# hhv-dcdarknet-varient-2.net
KiCad netlist of a schematic drawn in EAGLE
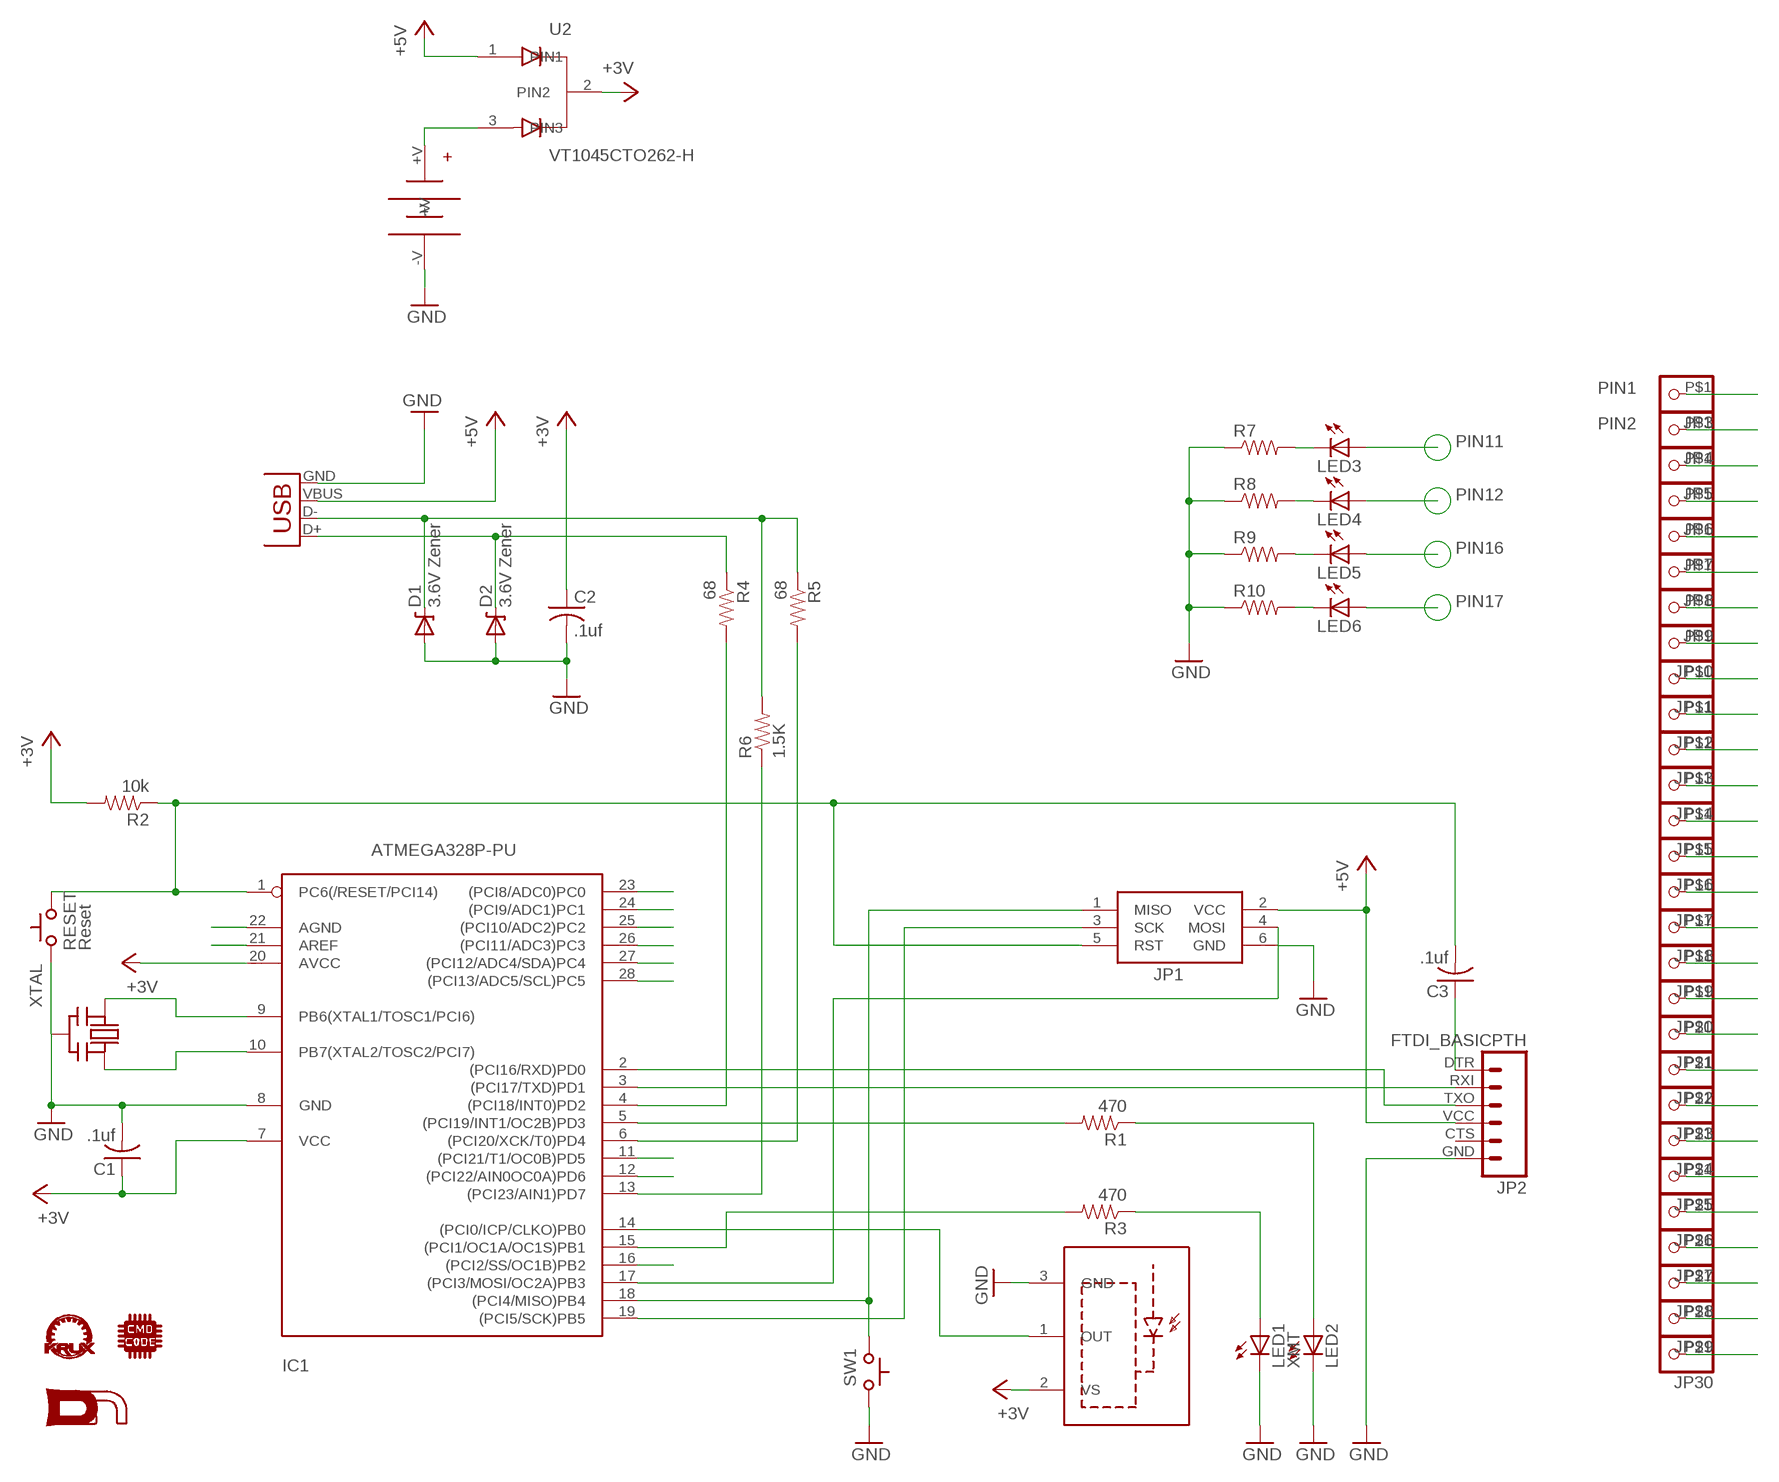
[diagram p0: schematic, sheet 1]

(export (version "E")
  (design (tool "Eeschema 10.0.6"))
  (components
    (comp (ref "C1")
      (value ".1uf")
      (footprint "eagle-import:C025-030X050")
      (libsource (lib "eagle-import") (part "C-US025-030X050"))
    )
    (comp (ref "C2")
      (value ".1uf")
      (footprint "eagle-import:C025-030X050")
      (libsource (lib "eagle-import") (part "C-US025-030X050"))
    )
    (comp (ref "C3")
      (value ".1uf")
      (footprint "eagle-import:C025-030X050")
      (libsource (lib "eagle-import") (part "C-US025-030X050"))
    )
    (comp (ref "D1")
      (value "3.6V Zener")
      (footprint "eagle-import:DIODE-ZENER")
      (libsource (lib "eagle-import") (part "DIODE-ZENERPTH"))
    )
    (comp (ref "D2")
      (value "3.6V Zener")
      (footprint "eagle-import:DIODE-ZENER")
      (libsource (lib "eagle-import") (part "DIODE-ZENERPTH"))
    )
    (comp (ref "IC1")
      (value "ATMEGA328P-PU")
      (footprint "eagle-import:DIL28-3")
      (libsource (lib "eagle-import") (part "ATMEGA168PV-10"))
    )
    (comp (ref "JP1")
      (value "JP1")
      (footprint "eagle-import:AVRISP")
      (libsource (lib "eagle-import") (part "AVRISP-6"))
    )
    (comp (ref "JP2")
      (value "FTDI_BASICPTH")
      (footprint "eagle-import:FTDI_BASIC")
      (libsource (lib "eagle-import") (part "FTDI_BASICPTH"))
    )
    (comp (ref "JP3")
      (value "PINHD-1X11X1_SQUARE")
      (footprint "eagle-import:1X1-SMALL_CUT")
      (libsource (lib "eagle-import") (part "PINHD-1X11X1_SQUARE"))
    )
    (comp (ref "JP4")
      (value "PINHD-1X11X1_SQUARE")
      (footprint "eagle-import:1X1-SMALL_CUT")
      (libsource (lib "eagle-import") (part "PINHD-1X11X1_SQUARE"))
    )
    (comp (ref "JP5")
      (value "PINHD-1X11X1_SQUARE")
      (footprint "eagle-import:1X1-SMALL_CUT")
      (libsource (lib "eagle-import") (part "PINHD-1X11X1_SQUARE"))
    )
    (comp (ref "JP6")
      (value "PINHD-1X11X1_SQUARE")
      (footprint "eagle-import:1X1-SMALL_CUT")
      (libsource (lib "eagle-import") (part "PINHD-1X11X1_SQUARE"))
    )
    (comp (ref "JP7")
      (value "PINHD-1X11X1_SQUARE")
      (footprint "eagle-import:1X1-SMALL_CUT")
      (libsource (lib "eagle-import") (part "PINHD-1X11X1_SQUARE"))
    )
    (comp (ref "JP8")
      (value "PINHD-1X11X1_SQUARE")
      (footprint "eagle-import:1X1-SMALL_CUT")
      (libsource (lib "eagle-import") (part "PINHD-1X11X1_SQUARE"))
    )
    (comp (ref "JP9")
      (value "PINHD-1X11X1_SQUARE")
      (footprint "eagle-import:1X1-SMALL_CUT")
      (libsource (lib "eagle-import") (part "PINHD-1X11X1_SQUARE"))
    )
    (comp (ref "JP10")
      (value "PINHD-1X11X1_SQUARE")
      (footprint "eagle-import:1X1-SMALL_CUT")
      (libsource (lib "eagle-import") (part "PINHD-1X11X1_SQUARE"))
    )
    (comp (ref "JP11")
      (value "PINHD-1X11X1_SQUARE")
      (footprint "eagle-import:1X1-SMALL_CUT")
      (libsource (lib "eagle-import") (part "PINHD-1X11X1_SQUARE"))
    )
    (comp (ref "JP12")
      (value "PINHD-1X11X1_SQUARE")
      (footprint "eagle-import:1X1-SMALL_CUT")
      (libsource (lib "eagle-import") (part "PINHD-1X11X1_SQUARE"))
    )
    (comp (ref "JP13")
      (value "PINHD-1X11X1_SQUARE")
      (footprint "eagle-import:1X1-SMALL_CUT")
      (libsource (lib "eagle-import") (part "PINHD-1X11X1_SQUARE"))
    )
    (comp (ref "JP14")
      (value "PINHD-1X11X1_SQUARE")
      (footprint "eagle-import:1X1-SMALL_CUT")
      (libsource (lib "eagle-import") (part "PINHD-1X11X1_SQUARE"))
    )
    (comp (ref "JP15")
      (value "PINHD-1X11X1_SQUARE")
      (footprint "eagle-import:1X1-SMALL_CUT")
      (libsource (lib "eagle-import") (part "PINHD-1X11X1_SQUARE"))
    )
    (comp (ref "JP16")
      (value "PINHD-1X11X1_SQUARE")
      (footprint "eagle-import:1X1-SMALL_CUT")
      (libsource (lib "eagle-import") (part "PINHD-1X11X1_SQUARE"))
    )
    (comp (ref "JP17")
      (value "PINHD-1X11X1_SQUARE")
      (footprint "eagle-import:1X1-SMALL_CUT")
      (libsource (lib "eagle-import") (part "PINHD-1X11X1_SQUARE"))
    )
    (comp (ref "JP18")
      (value "PINHD-1X11X1_SQUARE")
      (footprint "eagle-import:1X1-SMALL_CUT")
      (libsource (lib "eagle-import") (part "PINHD-1X11X1_SQUARE"))
    )
    (comp (ref "JP19")
      (value "PINHD-1X11X1_SQUARE")
      (footprint "eagle-import:1X1-SMALL_CUT")
      (libsource (lib "eagle-import") (part "PINHD-1X11X1_SQUARE"))
    )
    (comp (ref "JP20")
      (value "PINHD-1X11X1_SQUARE")
      (footprint "eagle-import:1X1-SMALL_CUT")
      (libsource (lib "eagle-import") (part "PINHD-1X11X1_SQUARE"))
    )
    (comp (ref "JP21")
      (value "PINHD-1X11X1_SQUARE")
      (footprint "eagle-import:1X1-SMALL_CUT")
      (libsource (lib "eagle-import") (part "PINHD-1X11X1_SQUARE"))
    )
    (comp (ref "JP22")
      (value "PINHD-1X11X1_SQUARE")
      (footprint "eagle-import:1X1-SMALL_CUT")
      (libsource (lib "eagle-import") (part "PINHD-1X11X1_SQUARE"))
    )
    (comp (ref "JP23")
      (value "PINHD-1X11X1_SQUARE")
      (footprint "eagle-import:1X1-SMALL_CUT")
      (libsource (lib "eagle-import") (part "PINHD-1X11X1_SQUARE"))
    )
    (comp (ref "JP24")
      (value "PINHD-1X11X1_SQUARE")
      (footprint "eagle-import:1X1-SMALL_CUT")
      (libsource (lib "eagle-import") (part "PINHD-1X11X1_SQUARE"))
    )
    (comp (ref "JP25")
      (value "PINHD-1X11X1_SQUARE")
      (footprint "eagle-import:1X1-SMALL_CUT")
      (libsource (lib "eagle-import") (part "PINHD-1X11X1_SQUARE"))
    )
    (comp (ref "JP26")
      (value "PINHD-1X11X1_SQUARE")
      (footprint "eagle-import:1X1-SMALL_CUT")
      (libsource (lib "eagle-import") (part "PINHD-1X11X1_SQUARE"))
    )
    (comp (ref "JP27")
      (value "PINHD-1X11X1_SQUARE")
      (footprint "eagle-import:1X1-SMALL_CUT")
      (libsource (lib "eagle-import") (part "PINHD-1X11X1_SQUARE"))
    )
    (comp (ref "JP28")
      (value "PINHD-1X11X1-SMALL")
      (footprint "eagle-import:1X1-SMALL")
      (libsource (lib "eagle-import") (part "PINHD-1X11X1-SMALL"))
    )
    (comp (ref "JP29")
      (value "PINHD-1X11X1_SQUARE")
      (footprint "eagle-import:1X1-SMALL_CUT")
      (libsource (lib "eagle-import") (part "PINHD-1X11X1_SQUARE"))
    )
    (comp (ref "JP30")
      (value "PINHD-1X11X1-SMALL")
      (footprint "eagle-import:1X1-SMALL")
      (libsource (lib "eagle-import") (part "PINHD-1X11X1-SMALL"))
    )
    (comp (ref "LED1")
      (value "XMT")
      (footprint "eagle-import:LED5MM-FLAT")
      (libsource (lib "eagle-import") (part "LED5MM-FLAT"))
    )
    (comp (ref "LED2")
      (value "LED5MM-FLAT")
      (footprint "eagle-import:LED5MM-FLAT")
      (libsource (lib "eagle-import") (part "LED5MM-FLAT"))
    )
    (comp (ref "LED3")
      (value "LED1206")
      (footprint "eagle-import:LED-1206")
      (libsource (lib "eagle-import") (part "SparkFun_LED1206"))
    )
    (comp (ref "LED4")
      (value "LED1206")
      (footprint "eagle-import:LED-1206")
      (libsource (lib "eagle-import") (part "SparkFun_LED1206"))
    )
    (comp (ref "LED5")
      (value "LED1206")
      (footprint "eagle-import:LED-1206")
      (libsource (lib "eagle-import") (part "SparkFun_LED1206"))
    )
    (comp (ref "LED6")
      (value "LED1206")
      (footprint "eagle-import:LED-1206")
      (libsource (lib "eagle-import") (part "SparkFun_LED1206"))
    )
    (comp (ref "R1")
      (value "470")
      (footprint "eagle-import:AXIAL-0.3")
      (libsource (lib "eagle-import") (part "RESISTORAXIAL-0.3"))
    )
    (comp (ref "R2")
      (value "10k")
      (footprint "eagle-import:AXIAL-0.3")
      (libsource (lib "eagle-import") (part "RESISTORAXIAL-0.3"))
    )
    (comp (ref "R3")
      (value "470")
      (footprint "eagle-import:AXIAL-0.3")
      (libsource (lib "eagle-import") (part "RESISTORAXIAL-0.3"))
    )
    (comp (ref "R4")
      (value "68")
      (footprint "eagle-import:AXIAL-0.3")
      (libsource (lib "eagle-import") (part "RESISTORAXIAL-0.3"))
    )
    (comp (ref "R5")
      (value "68")
      (footprint "eagle-import:AXIAL-0.3")
      (libsource (lib "eagle-import") (part "RESISTORAXIAL-0.3"))
    )
    (comp (ref "R6")
      (value "1.5K")
      (footprint "eagle-import:AXIAL-0.3")
      (libsource (lib "eagle-import") (part "RESISTORAXIAL-0.3"))
    )
    (comp (ref "R7")
      (value "RESISTOR1206")
      (footprint "eagle-import:1206")
      (libsource (lib "eagle-import") (part "SparkFun_RESISTOR1206"))
    )
    (comp (ref "R8")
      (value "RESISTOR1206")
      (footprint "eagle-import:1206")
      (libsource (lib "eagle-import") (part "SparkFun_RESISTOR1206"))
    )
    (comp (ref "R9")
      (value "RESISTOR1206")
      (footprint "eagle-import:1206")
      (libsource (lib "eagle-import") (part "SparkFun_RESISTOR1206"))
    )
    (comp (ref "R10")
      (value "RESISTOR1206")
      (footprint "eagle-import:1206")
      (libsource (lib "eagle-import") (part "SparkFun_RESISTOR1206"))
    )
    (comp (ref "RESET")
      (value "Reset")
      (footprint "eagle-import:TACTILE-2PIN")
      (libsource (lib "eagle-import") (part "SWITCH_TACTILETACTILE-2PIN"))
    )
    (comp (ref "SW1")
      (value "SWITCH_TACTILETACTILE-2PIN")
      (footprint "eagle-import:TACTILE-2PIN")
      (libsource (lib "eagle-import") (part "SWITCH_TACTILETACTILE-2PIN"))
    )
    (comp (ref "U$1")
      (value "DN_LOGO")
      (footprint "eagle-import:DN_LOGO")
      (libsource (lib "eagle-import") (part "DN_LOGO"))
    )
    (comp (ref "U$2")
      (value "CMDC0DE_LOGO")
      (footprint "eagle-import:CMDC0DE")
      (libsource (lib "eagle-import") (part "CMDC0DE_LOGO"))
    )
    (comp (ref "U$3")
      (value "KRUX_LOGO")
      (footprint "eagle-import:KRUX_LOGO")
      (libsource (lib "eagle-import") (part "KRUX_LOGO"))
    )
    (comp (ref "U$5")
      (value "12BH423-GR3-CELL_NOBORDER")
      (footprint "eagle-import:3-AAA-CELL_NOBORDER")
      (libsource (lib "eagle-import") (part "12BH423-GR3-CELL_NOBORDER"))
    )
    (comp (ref "U1")
      (value "RCV")
      (footprint "eagle-import:IR-MODULE")
      (libsource (lib "eagle-import") (part "SOP22"))
    )
    (comp (ref "U2")
      (value "VT1045CTO262-H")
      (footprint "eagle-import:TO262-H")
      (libsource (lib "eagle-import") (part "VT1045CTO262-H"))
    )
    (comp (ref "X2")
      (value "USB")
      (footprint "eagle-import:USB-B-PTH")
      (libsource (lib "eagle-import") (part "USBPTH"))
    )
    (comp (ref "XTAL")
      (value "CERMOSCILL-THM")
      (footprint "eagle-import:CERM_OSC")
      (libsource (lib "eagle-import") (part "CERMOSCILL-THM"))
    )
  )
  (nets
    (net (code "1") (name "+3V") (class "Default")
      (node (ref "C1") (pin "1") (pinfunction "1_1") (pintype "passive"))
      (node (ref "C2") (pin "1") (pinfunction "1_1") (pintype "passive"))
      (node (ref "IC1") (pin "20") (pinfunction "AVCC_20") (pintype "bidirectional"))
      (node (ref "IC1") (pin "7") (pinfunction "VCC_7") (pintype "bidirectional"))
      (node (ref "JP22") (pin "P$1") (pinfunction "1_P$1") (pintype "passive"))
      (node (ref "JP9") (pin "P$1") (pinfunction "1_P$1") (pintype "passive"))
      (node (ref "R2") (pin "P$2") (pinfunction "2_P$2") (pintype "passive"))
      (node (ref "U1") (pin "2") (pinfunction "VS_2") (pintype "bidirectional"))
      (node (ref "U2") (pin "2") (pinfunction "PIN2_2") (pintype "bidirectional"))
    )
    (net (code "2") (name "+5V") (class "Default")
      (node (ref "JP1") (pin "2") (pinfunction "VCC_2") (pintype "power_in"))
      (node (ref "JP2") (pin "VCC") (pinfunction "4_VCC") (pintype "passive"))
      (node (ref "U2") (pin "1") (pinfunction "PIN1_1") (pintype "bidirectional"))
      (node (ref "X2") (pin "VBUS") (pinfunction "VBUS_VBUS") (pintype "bidirectional"))
    )
    (net (code "3") (name "/PIN1") (class "Default")
      (node (ref "C3") (pin "2") (pinfunction "2_2") (pintype "passive"))
      (node (ref "IC1") (pin "1") (pinfunction "PC6(/RESET/PCI14)_1") (pintype "bidirectional"))
      (node (ref "JP1") (pin "5") (pinfunction "RST_5") (pintype "output"))
      (node (ref "JP3") (pin "P$1") (pinfunction "1_P$1") (pintype "passive"))
      (node (ref "R2") (pin "P$1") (pinfunction "1_P$1") (pintype "passive"))
      (node (ref "RESET") (pin "P$1") (pinfunction "A_P$1") (pintype "passive"))
    )
    (net (code "4") (name "/PIN2") (class "Default")
      (node (ref "IC1") (pin "2") (pinfunction "(PCI16/RXD)PD0_2") (pintype "bidirectional"))
      (node (ref "JP2") (pin "TXO") (pinfunction "3_TXO") (pintype "passive"))
      (node (ref "JP4") (pin "P$1") (pinfunction "1_P$1") (pintype "passive"))
    )
    (net (code "5") (name "/PIN3") (class "Default")
      (node (ref "IC1") (pin "3") (pinfunction "(PCI17/TXD)PD1_3") (pintype "bidirectional"))
      (node (ref "JP2") (pin "RXI") (pinfunction "2_RXI") (pintype "passive"))
      (node (ref "JP5") (pin "P$1") (pinfunction "1_P$1") (pintype "passive"))
    )
    (net (code "6") (name "/PIN4") (class "Default")
      (node (ref "IC1") (pin "4") (pinfunction "(PCI18/INT0)PD2_4") (pintype "bidirectional"))
      (node (ref "JP6") (pin "P$1") (pinfunction "1_P$1") (pintype "passive"))
      (node (ref "R4") (pin "P$2") (pinfunction "2_P$2") (pintype "passive"))
    )
    (net (code "7") (name "/PIN5") (class "Default")
      (node (ref "IC1") (pin "5") (pinfunction "(PCI19/INT1/OC2B)PD3_5") (pintype "bidirectional"))
      (node (ref "JP7") (pin "P$1") (pinfunction "1_P$1") (pintype "passive"))
      (node (ref "R1") (pin "P$2") (pinfunction "2_P$2") (pintype "passive"))
    )
    (net (code "8") (name "/PIN6") (class "Default")
      (node (ref "IC1") (pin "6") (pinfunction "(PCI20/XCK/T0)PD4_6") (pintype "bidirectional"))
      (node (ref "JP8") (pin "P$1") (pinfunction "1_P$1") (pintype "passive"))
      (node (ref "R5") (pin "P$2") (pinfunction "2_P$2") (pintype "passive"))
    )
    (net (code "9") (name "/PIN9") (class "Default")
      (node (ref "IC1") (pin "9") (pinfunction "PB6(XTAL1/TOSC1/PCI6)_9") (pintype "bidirectional"))
      (node (ref "JP11") (pin "P$1") (pinfunction "1_P$1") (pintype "passive"))
      (node (ref "XTAL") (pin "P$1") (pinfunction "IN_P$1") (pintype "bidirectional"))
    )
    (net (code "10") (name "/PIN10") (class "Default")
      (node (ref "IC1") (pin "10") (pinfunction "PB7(XTAL2/TOSC2/PCI7)_10") (pintype "bidirectional"))
      (node (ref "JP12") (pin "P$1") (pinfunction "1_P$1") (pintype "passive"))
      (node (ref "XTAL") (pin "P$3") (pinfunction "OUT_P$3") (pintype "bidirectional"))
    )
    (net (code "11") (name "/PIN11") (class "Default")
      (node (ref "IC1") (pin "11") (pinfunction "(PCI21/T1/OC0B)PD5_11") (pintype "bidirectional"))
      (node (ref "JP13") (pin "P$1") (pinfunction "1_P$1") (pintype "passive"))
      (node (ref "LED3") (pin "A") (pinfunction "A_A") (pintype "passive"))
    )
    (net (code "12") (name "/PIN12") (class "Default")
      (node (ref "IC1") (pin "12") (pinfunction "(PCI22/AIN0OC0A)PD6_12") (pintype "bidirectional"))
      (node (ref "JP14") (pin "P$1") (pinfunction "1_P$1") (pintype "passive"))
      (node (ref "LED4") (pin "A") (pinfunction "A_A") (pintype "passive"))
    )
    (net (code "13") (name "/PIN13") (class "Default")
      (node (ref "IC1") (pin "13") (pinfunction "(PCI23/AIN1)PD7_13") (pintype "bidirectional"))
      (node (ref "JP15") (pin "P$1") (pinfunction "1_P$1") (pintype "passive"))
      (node (ref "R6") (pin "P$1") (pinfunction "1_P$1") (pintype "passive"))
    )
    (net (code "14") (name "/PIN14") (class "Default")
      (node (ref "IC1") (pin "14") (pinfunction "(PCI0/ICP/CLKO)PB0_14") (pintype "bidirectional"))
      (node (ref "JP16") (pin "P$1") (pinfunction "1_P$1") (pintype "passive"))
      (node (ref "U1") (pin "1") (pinfunction "OUT_1") (pintype "bidirectional"))
    )
    (net (code "15") (name "/PIN15") (class "Default")
      (node (ref "IC1") (pin "15") (pinfunction "(PCI1/OC1A/OC1S)PB1_15") (pintype "bidirectional"))
      (node (ref "JP17") (pin "P$1") (pinfunction "1_P$1") (pintype "passive"))
      (node (ref "R3") (pin "P$2") (pinfunction "2_P$2") (pintype "passive"))
    )
    (net (code "16") (name "/PIN16") (class "Default")
      (node (ref "IC1") (pin "16") (pinfunction "(PCI2/SS/OC1B)PB2_16") (pintype "bidirectional"))
      (node (ref "JP18") (pin "P$1") (pinfunction "1_P$1") (pintype "passive"))
      (node (ref "LED5") (pin "A") (pinfunction "A_A") (pintype "passive"))
    )
    (net (code "17") (name "/PIN17") (class "Default")
      (node (ref "IC1") (pin "17") (pinfunction "(PCI3/MOSI/OC2A)PB3_17") (pintype "bidirectional"))
      (node (ref "JP1") (pin "4") (pinfunction "MOSI_4") (pintype "output"))
      (node (ref "JP19") (pin "P$1") (pinfunction "1_P$1") (pintype "passive"))
      (node (ref "LED6") (pin "A") (pinfunction "A_A") (pintype "passive"))
    )
    (net (code "18") (name "/PIN18") (class "Default")
      (node (ref "IC1") (pin "18") (pinfunction "(PCI4/MISO)PB4_18") (pintype "bidirectional"))
      (node (ref "JP1") (pin "1") (pinfunction "MISO_1") (pintype "input"))
      (node (ref "JP20") (pin "P$1") (pinfunction "1_P$1") (pintype "passive"))
      (node (ref "SW1") (pin "P$2") (pinfunction "C_P$2") (pintype "passive"))
    )
    (net (code "19") (name "/PIN19") (class "Default")
      (node (ref "IC1") (pin "19") (pinfunction "(PCI5/SCK)PB5_19") (pintype "bidirectional"))
      (node (ref "JP1") (pin "3") (pinfunction "SCK_3") (pintype "output"))
      (node (ref "JP21") (pin "P$1") (pinfunction "1_P$1") (pintype "passive"))
    )
    (net (code "20") (name "/PIN21") (class "Default")
      (node (ref "IC1") (pin "21") (pinfunction "AREF_21") (pintype "bidirectional"))
      (node (ref "JP23") (pin "P$1") (pinfunction "1_P$1") (pintype "passive"))
    )
    (net (code "21") (name "/PIN22") (class "Default")
      (node (ref "IC1") (pin "22") (pinfunction "AGND_22") (pintype "bidirectional"))
      (node (ref "JP24") (pin "P$1") (pinfunction "1_P$1") (pintype "passive"))
    )
    (net (code "22") (name "/PIN23") (class "Default")
      (node (ref "IC1") (pin "23") (pinfunction "(PCI8/ADC0)PC0_23") (pintype "bidirectional"))
      (node (ref "JP25") (pin "P$1") (pinfunction "1_P$1") (pintype "passive"))
    )
    (net (code "23") (name "/PIN24") (class "Default")
      (node (ref "IC1") (pin "24") (pinfunction "(PCI9/ADC1)PC1_24") (pintype "bidirectional"))
      (node (ref "JP26") (pin "P$1") (pinfunction "1_P$1") (pintype "passive"))
    )
    (net (code "24") (name "/PIN25") (class "Default")
      (node (ref "IC1") (pin "25") (pinfunction "(PCI10/ADC2)PC2_25") (pintype "bidirectional"))
      (node (ref "JP27") (pin "P$1") (pinfunction "1_P$1") (pintype "passive"))
    )
    (net (code "25") (name "/PIN26") (class "Default")
      (node (ref "IC1") (pin "26") (pinfunction "(PCI11/ADC3)PC3_26") (pintype "bidirectional"))
      (node (ref "JP28") (pin "P$1") (pinfunction "1_P$1") (pintype "passive"))
    )
    (net (code "26") (name "/PIN27") (class "Default")
      (node (ref "IC1") (pin "27") (pinfunction "(PCI12/ADC4/SDA)PC4_27") (pintype "bidirectional"))
      (node (ref "JP29") (pin "P$1") (pinfunction "1_P$1") (pintype "passive"))
    )
    (net (code "27") (name "/PIN28") (class "Default")
      (node (ref "IC1") (pin "28") (pinfunction "(PCI13/ADC5/SCL)PC5_28") (pintype "bidirectional"))
      (node (ref "JP30") (pin "P$1") (pinfunction "1_P$1") (pintype "passive"))
    )
    (net (code "28") (name "GND") (class "Default")
      (node (ref "C1") (pin "2") (pinfunction "2_2") (pintype "passive"))
      (node (ref "C2") (pin "2") (pinfunction "2_2") (pintype "passive"))
      (node (ref "D1") (pin "P$2") (pinfunction "A_P$2") (pintype "passive"))
      (node (ref "D2") (pin "P$2") (pinfunction "A_P$2") (pintype "passive"))
      (node (ref "IC1") (pin "8") (pinfunction "GND_8") (pintype "bidirectional"))
      (node (ref "JP1") (pin "6") (pinfunction "GND_6") (pintype "power_in"))
      (node (ref "JP10") (pin "P$1") (pinfunction "1_P$1") (pintype "passive"))
      (node (ref "JP2") (pin "GND") (pinfunction "6_GND") (pintype "passive"))
      (node (ref "LED1") (pin "K") (pinfunction "C_K") (pintype "passive"))
      (node (ref "LED2") (pin "K") (pinfunction "C_K") (pintype "passive"))
      (node (ref "R10") (pin "1") (pinfunction "1_1") (pintype "passive"))
      (node (ref "R7") (pin "1") (pinfunction "1_1") (pintype "passive"))
      (node (ref "R8") (pin "1") (pinfunction "1_1") (pintype "passive"))
      (node (ref "R9") (pin "1") (pinfunction "1_1") (pintype "passive"))
      (node (ref "RESET") (pin "P$2") (pinfunction "C_P$2") (pintype "passive"))
      (node (ref "SW1") (pin "P$1") (pinfunction "A_P$1") (pintype "passive"))
      (node (ref "U$5") (pin "-V") (pinfunction "-V_-V") (pintype "bidirectional"))
      (node (ref "U1") (pin "3") (pinfunction "GND_3") (pintype "bidirectional"))
      (node (ref "X2") (pin "GND") (pinfunction "GND_GND") (pintype "bidirectional"))
      (node (ref "XTAL") (pin "P$2") (pinfunction "GND_P$2") (pintype "bidirectional"))
    )
    (net (code "29") (name "Net-(D1-C)") (class "Default")
      (node (ref "D1") (pin "P$1") (pinfunction "C_P$1") (pintype "passive"))
      (node (ref "R5") (pin "P$1") (pinfunction "1_P$1") (pintype "passive"))
      (node (ref "R6") (pin "P$2") (pinfunction "2_P$2") (pintype "passive"))
      (node (ref "X2") (pin "D-") (pinfunction "D-_D-") (pintype "bidirectional"))
    )
    (net (code "30") (name "Net-(D2-C)") (class "Default")
      (node (ref "D2") (pin "P$1") (pinfunction "C_P$1") (pintype "passive"))
      (node (ref "R4") (pin "P$1") (pinfunction "1_P$1") (pintype "passive"))
      (node (ref "X2") (pin "D+") (pinfunction "D+_D+") (pintype "bidirectional"))
    )
    (net (code "31") (name "Net-(JP2-1)") (class "Default")
      (node (ref "C3") (pin "1") (pinfunction "1_1") (pintype "passive"))
      (node (ref "JP2") (pin "DTR") (pinfunction "1_DTR") (pintype "passive"))
    )
    (net (code "32") (name "Net-(LED3-PadC)") (class "Default")
      (node (ref "LED3") (pin "C") (pinfunction "C_C") (pintype "passive"))
      (node (ref "R7") (pin "2") (pinfunction "2_2") (pintype "passive"))
    )
    (net (code "33") (name "Net-(LED4-PadC)") (class "Default")
      (node (ref "LED4") (pin "C") (pinfunction "C_C") (pintype "passive"))
      (node (ref "R8") (pin "2") (pinfunction "2_2") (pintype "passive"))
    )
    (net (code "34") (name "Net-(LED5-PadC)") (class "Default")
      (node (ref "LED5") (pin "C") (pinfunction "C_C") (pintype "passive"))
      (node (ref "R9") (pin "2") (pinfunction "2_2") (pintype "passive"))
    )
    (net (code "35") (name "Net-(LED6-PadC)") (class "Default")
      (node (ref "LED6") (pin "C") (pinfunction "C_C") (pintype "passive"))
      (node (ref "R10") (pin "2") (pinfunction "2_2") (pintype "passive"))
    )
    (net (code "36") (name "Net-(R1-1)") (class "Default")
      (node (ref "LED2") (pin "A") (pinfunction "A_A") (pintype "passive"))
      (node (ref "R1") (pin "P$1") (pinfunction "1_P$1") (pintype "passive"))
    )
    (net (code "37") (name "Net-(R3-1)") (class "Default")
      (node (ref "LED1") (pin "A") (pinfunction "A_A") (pintype "passive"))
      (node (ref "R3") (pin "P$1") (pinfunction "1_P$1") (pintype "passive"))
    )
    (net (code "38") (name "Net-(U2-PIN3)") (class "Default")
      (node (ref "U$5") (pin "+V") (pinfunction "+V_+V") (pintype "bidirectional"))
      (node (ref "U2") (pin "3") (pinfunction "PIN3_3") (pintype "bidirectional"))
    )
    (net (code "39") (name "unconnected-(JP2-5-PadCTS)") (class "Default")
      (node (ref "JP2") (pin "CTS") (pinfunction "5_CTS") (pintype "passive"))
    )
  )
)
